# rear_ultrasonic_radar.net
KiCad netlist of a schematic drawn in Altium Designer
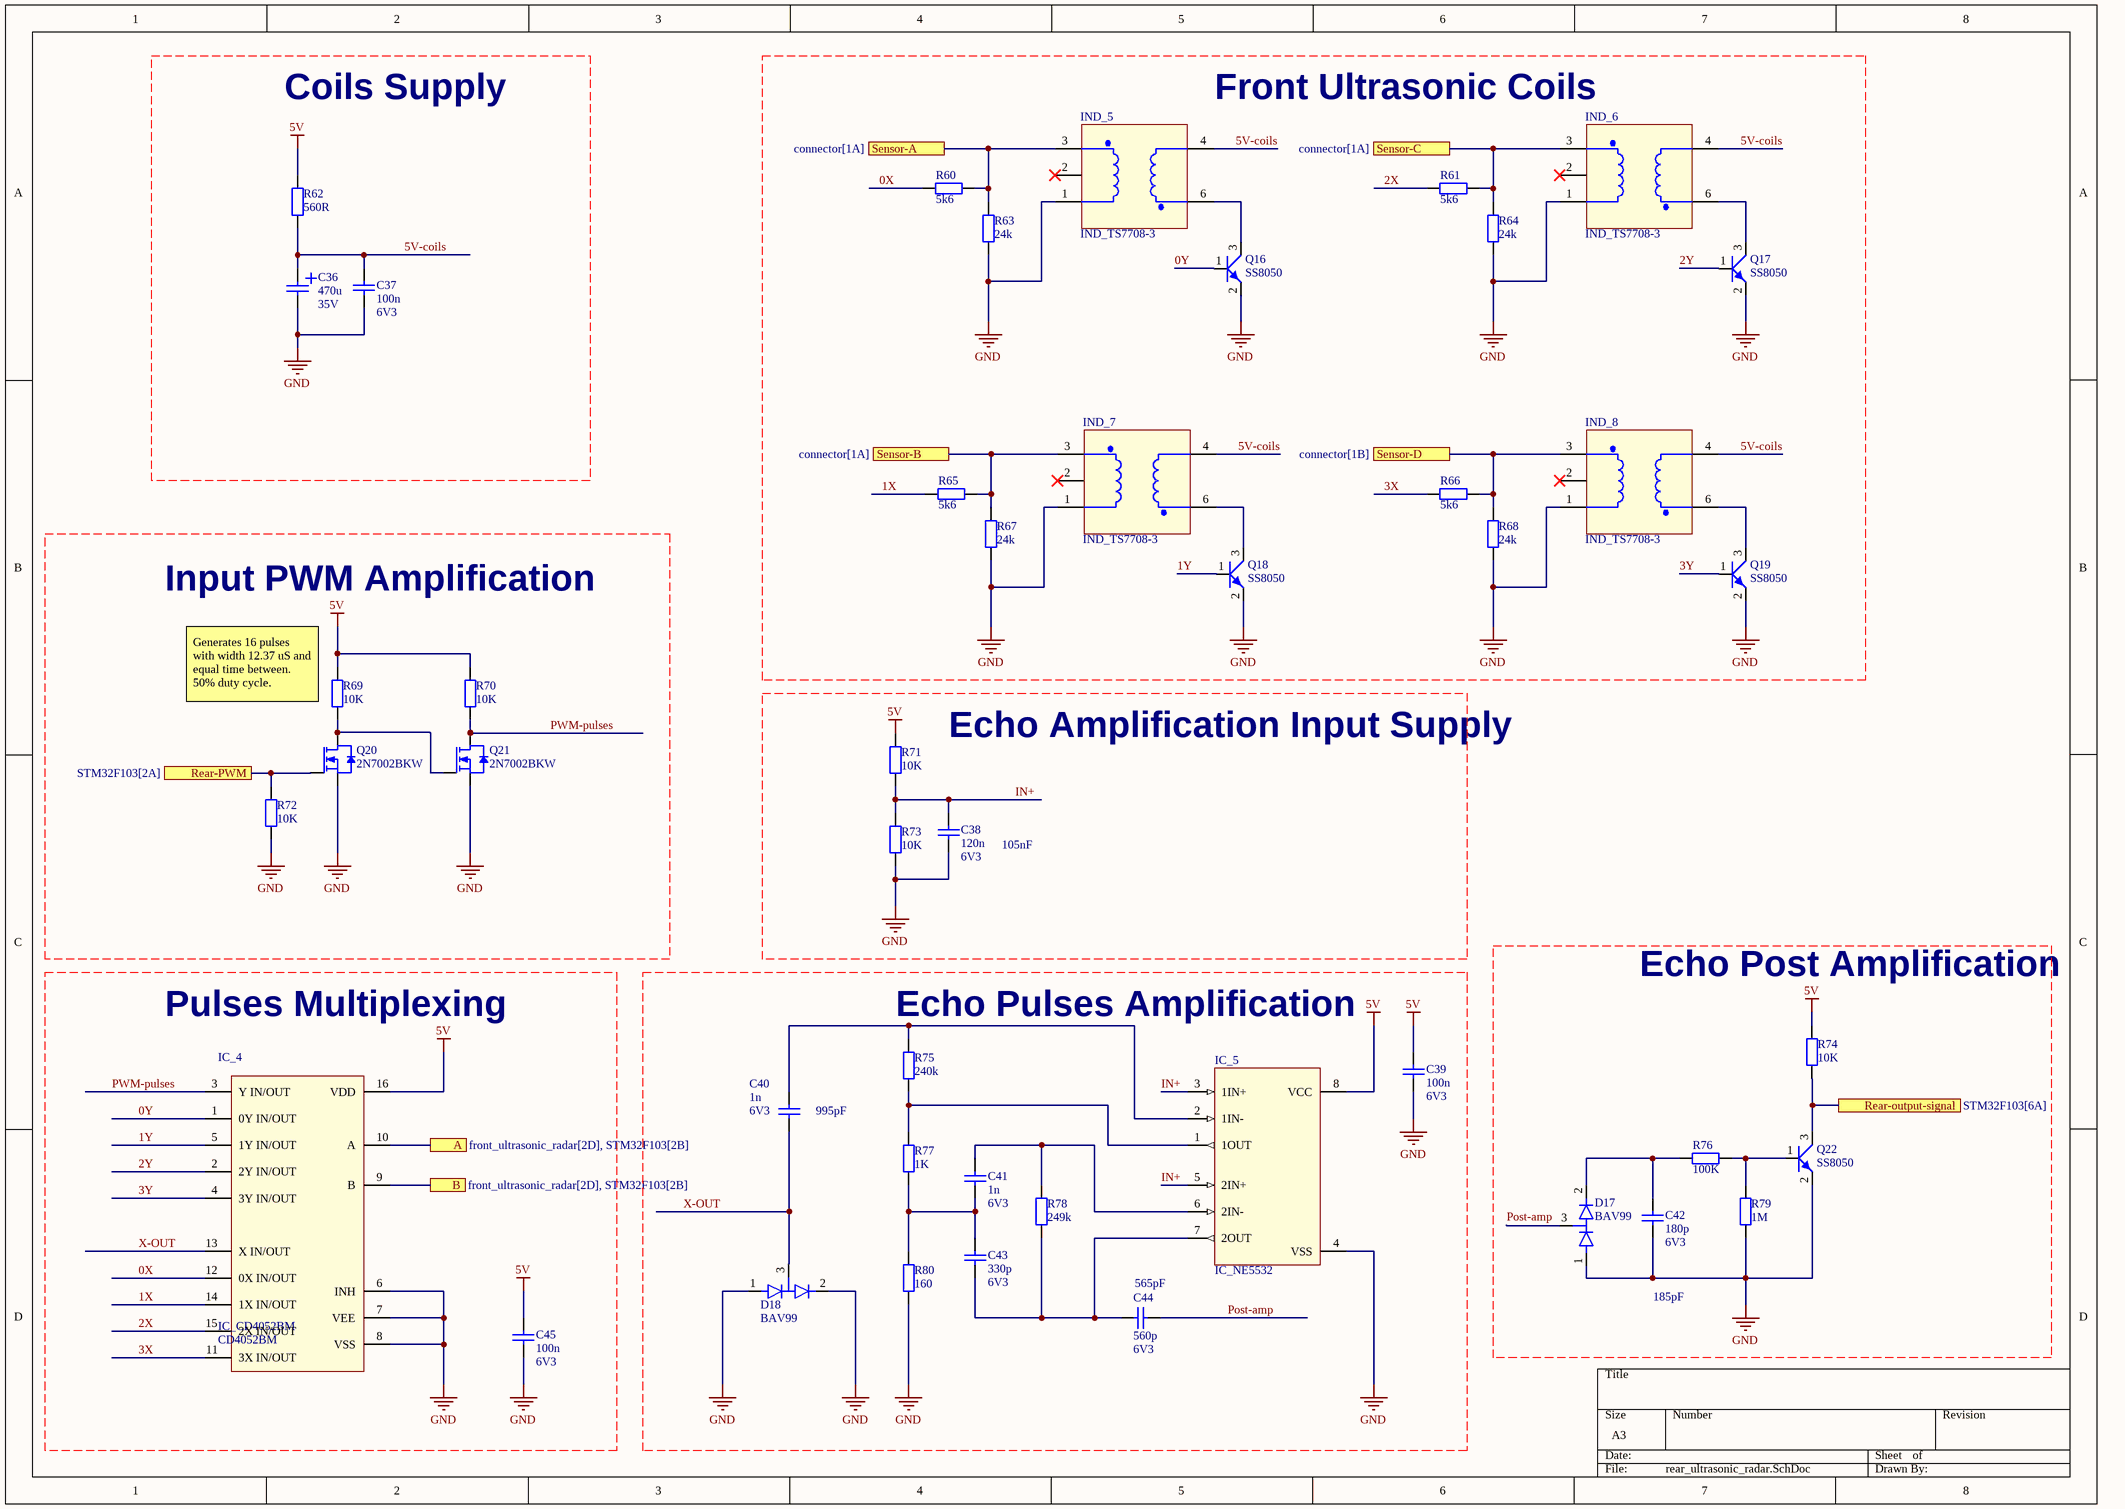
[diagram p0: rear_ultrasonic_radar.SchDoc]

(export (version "E")
  (design (tool "Eeschema 10.0.6"))
  (components
    (comp (ref "C36")
      (value "CAP_POL")
      (footprint "CAP_Panasonic_EEE-FK1V471SP")
      (description "Aluminium Electrolytic Capacitors - SMD 35volts 470uF SMD AEC-Q200 Reflow Only")
      (fields
        (field (name "VALUE1") "470u")
        (field (name "VALUE2") "35V")
        (field (name "MANUFACTURER") "Panasonic")
      )
      (libsource (lib "DSW_Lib") (part "CAP_POL"))
    )
    (comp (ref "C37")
      (value "CAP")
      (footprint "CAPC2012X88N")
      (description "X7R 10% 0805")
      (fields
        (field (name "VALUE1") "100n")
        (field (name "VALUE2") "6V3")
        (field (name "MANUFACTURER") "KEMET")
      )
      (libsource (lib "DSW_Lib") (part "CAP"))
    )
    (comp (ref "C38")
      (value "CAP")
      (footprint "CAPC2012X88N")
      (description "X7R 10% 0805")
      (fields
        (field (name "VALUE1") "120n")
        (field (name "VALUE2") "6V3")
        (field (name "MANUFACTURER") "KEMET")
      )
      (libsource (lib "DSW_Lib") (part "CAP"))
    )
    (comp (ref "C39")
      (value "CAP")
      (footprint "CAPC2012X88N")
      (description "X7R 10% 0805")
      (fields
        (field (name "VALUE1") "100n")
        (field (name "VALUE2") "6V3")
        (field (name "MANUFACTURER") "KEMET")
      )
      (libsource (lib "DSW_Lib") (part "CAP"))
    )
    (comp (ref "C40")
      (value "CAP")
      (footprint "CAPC2012X88N")
      (description "X7R 10% 0805")
      (fields
        (field (name "VALUE1") "1n")
        (field (name "VALUE2") "6V3")
        (field (name "MANUFACTURER") "KEMET")
      )
      (libsource (lib "DSW_Lib") (part "CAP"))
    )
    (comp (ref "C41")
      (value "CAP")
      (footprint "CAPC2012X88N")
      (description "X7R 10% 0805")
      (fields
        (field (name "VALUE1") "1n")
        (field (name "VALUE2") "6V3")
        (field (name "MANUFACTURER") "KEMET")
      )
      (libsource (lib "DSW_Lib") (part "CAP"))
    )
    (comp (ref "C42")
      (value "CAP")
      (footprint "CAPC2012X88N")
      (description "X7R 10% 0805")
      (fields
        (field (name "VALUE1") "180p")
        (field (name "VALUE2") "6V3")
        (field (name "MANUFACTURER") "KEMET")
      )
      (libsource (lib "DSW_Lib") (part "CAP"))
    )
    (comp (ref "C43")
      (value "CAP")
      (footprint "CAPC2012X88N")
      (description "X7R 10% 0805")
      (fields
        (field (name "VALUE1") "330p")
        (field (name "VALUE2") "6V3")
        (field (name "MANUFACTURER") "KEMET")
      )
      (libsource (lib "DSW_Lib") (part "CAP"))
    )
    (comp (ref "C44")
      (value "CAP")
      (footprint "CAPC2012X88N")
      (description "X7R 10% 0805")
      (fields
        (field (name "VALUE1") "560p")
        (field (name "VALUE2") "6V3")
        (field (name "MANUFACTURER") "KEMET")
      )
      (libsource (lib "DSW_Lib") (part "CAP"))
    )
    (comp (ref "C45")
      (value "CAP")
      (footprint "CAPC2012X88N")
      (description "X7R 10% 0805")
      (fields
        (field (name "VALUE1") "100n")
        (field (name "VALUE2") "6V3")
        (field (name "MANUFACTURER") "KEMET")
      )
      (libsource (lib "DSW_Lib") (part "CAP"))
    )
    (comp (ref "D17")
      (value "High-speed double diode")
      (footprint "DIO_BAV99-SOT23")
      (fields (field (name "VALUE1") "BAV99") (field (name "MANUFACTURER") "Philips"))
      (libsource (lib "DSW_Lib") (part "DIO_BAV99"))
    )
    (comp (ref "D18")
      (value "High-speed double diode")
      (footprint "DIO_BAV99-SOT23")
      (fields (field (name "VALUE1") "BAV99") (field (name "MANUFACTURER") "Philips"))
      (libsource (lib "DSW_Lib") (part "DIO_BAV99"))
    )
    (comp (ref "IC_4")
      (value "IC_CD4052BM")
      (footprint "SOP-16")
      (description "Dual 4-Channel Analog Multiplexer/Demultiplexer")
      (fields (field (name "VALUE1") "CD4052BM") (field (name "MANUFACTURER") "Texas Instruments"))
      (libsource (lib "DSW_Lib") (part "IC_CD4052BM"))
    )
    (comp (ref "IC_5")
      (value "IC_NE5532")
      (description "Dual low-noise operational amplifier ")
      (libsource (lib "IC_NE5532") (part "IC_NE5532"))
    )
    (comp (ref "IND_5")
      (value "IND_TS7708-3")
      (description "12times Amplifying Transformer,IFT Inductors for Ultrasonic Sensors")
      (libsource (lib "IND_TS7708-3") (part "IND_TS7708-3"))
    )
    (comp (ref "IND_6")
      (value "IND_TS7708-3")
      (description "12times Amplifying Transformer,IFT Inductors for Ultrasonic Sensors")
      (libsource (lib "IND_TS7708-3") (part "IND_TS7708-3"))
    )
    (comp (ref "IND_7")
      (value "IND_TS7708-3")
      (description "12times Amplifying Transformer,IFT Inductors for Ultrasonic Sensors")
      (libsource (lib "IND_TS7708-3") (part "IND_TS7708-3"))
    )
    (comp (ref "IND_8")
      (value "IND_TS7708-3")
      (description "12times Amplifying Transformer,IFT Inductors for Ultrasonic Sensors")
      (libsource (lib "IND_TS7708-3") (part "IND_TS7708-3"))
    )
    (comp (ref "Q16")
      (value "TRS_NPN_123")
      (footprint "SOT23")
      (description "Bipolar Transistors - BJT NPN TRANSISTOR 1.5A 40V")
      (fields (field (name "VALUE1") "SS8050") (field (name "MANUFACTURER") "KooChin"))
      (libsource (lib "DSW_Lib") (part "TRS_NPN_123"))
    )
    (comp (ref "Q17")
      (value "TRS_NPN_123")
      (footprint "SOT23")
      (description "Bipolar Transistors - BJT NPN TRANSISTOR 1.5A 40V")
      (fields (field (name "VALUE1") "SS8050") (field (name "MANUFACTURER") "KooChin"))
      (libsource (lib "DSW_Lib") (part "TRS_NPN_123"))
    )
    (comp (ref "Q18")
      (value "TRS_NPN_123")
      (footprint "SOT23")
      (description "Bipolar Transistors - BJT NPN TRANSISTOR 1.5A 40V")
      (fields (field (name "VALUE1") "SS8050") (field (name "MANUFACTURER") "KooChin"))
      (libsource (lib "DSW_Lib") (part "TRS_NPN_123"))
    )
    (comp (ref "Q19")
      (value "TRS_NPN_123")
      (footprint "SOT23")
      (description "Bipolar Transistors - BJT NPN TRANSISTOR 1.5A 40V")
      (fields (field (name "VALUE1") "SS8050") (field (name "MANUFACTURER") "KooChin"))
      (libsource (lib "DSW_Lib") (part "TRS_NPN_123"))
    )
    (comp (ref "Q20")
      (value "TRS_FETN_123")
      (footprint "SOT65P210X110-3N")
      (description "NXP - 2N7002BKW - MOSFET, N CH, 60V, 0.31A, SOT323")
      (fields (field (name "VALUE1") "2N7002BKW") (field (name "MANUFACTURER") "NXP"))
      (libsource (lib "DSW_Lib") (part "TRS_FETN_123"))
    )
    (comp (ref "Q21")
      (value "TRS_FETN_123")
      (footprint "SOT65P210X110-3N")
      (description "NXP - 2N7002BKW - MOSFET, N CH, 60V, 0.31A, SOT323")
      (fields (field (name "VALUE1") "2N7002BKW") (field (name "MANUFACTURER") "NXP"))
      (libsource (lib "DSW_Lib") (part "TRS_FETN_123"))
    )
    (comp (ref "Q22")
      (value "TRS_NPN_123")
      (footprint "SOT23")
      (description "Bipolar Transistors - BJT NPN TRANSISTOR 1.5A 40V")
      (fields (field (name "VALUE1") "SS8050") (field (name "MANUFACTURER") "KooChin"))
      (libsource (lib "DSW_Lib") (part "TRS_NPN_123"))
    )
    (comp (ref "R60")
      (value "RES")
      (footprint "RESC2012X60N")
      (description "RESISTOR, 0805, 5k6, 1%, SMD")
      (fields (field (name "VALUE1") "5k6") (field (name "MANUFACTURER") "Yageo"))
      (libsource (lib "") (part "RES_2"))
    )
    (comp (ref "R61")
      (value "RES")
      (footprint "RESC2012X60N")
      (description "RESISTOR, 0805, 5k6, 1%, SMD")
      (fields (field (name "VALUE1") "5k6") (field (name "MANUFACTURER") "Yageo"))
      (libsource (lib "") (part "RES_2"))
    )
    (comp (ref "R62")
      (value "RES")
      (footprint "RESC2012X60N")
      (description "RESISTOR, 0805, 560R, 1%, SMD")
      (fields (field (name "VALUE1") "560R") (field (name "MANUFACTURER") "Yageo"))
      (libsource (lib "DSW_Lib") (part "RES"))
    )
    (comp (ref "R63")
      (value "RES")
      (footprint "RESC2012X60N")
      (description "RESISTOR, 0805, 24k, 1%, SMD")
      (fields (field (name "VALUE1") "24k") (field (name "MANUFACTURER") "Yageo"))
      (libsource (lib "DSW_Lib") (part "RES"))
    )
    (comp (ref "R64")
      (value "RES")
      (footprint "RESC2012X60N")
      (description "RESISTOR, 0805, 24k, 1%, SMD")
      (fields (field (name "VALUE1") "24k") (field (name "MANUFACTURER") "Yageo"))
      (libsource (lib "DSW_Lib") (part "RES"))
    )
    (comp (ref "R65")
      (value "RES")
      (footprint "RESC2012X60N")
      (description "RESISTOR, 0805, 5k6, 1%, SMD")
      (fields (field (name "VALUE1") "5k6") (field (name "MANUFACTURER") "Yageo"))
      (libsource (lib "") (part "RES_2"))
    )
    (comp (ref "R66")
      (value "RES")
      (footprint "RESC2012X60N")
      (description "RESISTOR, 0805, 5k6, 1%, SMD")
      (fields (field (name "VALUE1") "5k6") (field (name "MANUFACTURER") "Yageo"))
      (libsource (lib "") (part "RES_2"))
    )
    (comp (ref "R67")
      (value "RES")
      (footprint "RESC2012X60N")
      (description "RESISTOR, 0805, 24k, 1%, SMD")
      (fields (field (name "VALUE1") "24k") (field (name "MANUFACTURER") "Yageo"))
      (libsource (lib "DSW_Lib") (part "RES"))
    )
    (comp (ref "R68")
      (value "RES")
      (footprint "RESC2012X60N")
      (description "RESISTOR, 0805, 24k, 1%, SMD")
      (fields (field (name "VALUE1") "24k") (field (name "MANUFACTURER") "Yageo"))
      (libsource (lib "DSW_Lib") (part "RES"))
    )
    (comp (ref "R69")
      (value "RES")
      (footprint "RESC2012X60N")
      (description "RESISTOR, 0805, 10K, 1%, SMD")
      (fields (field (name "VALUE1") "10K") (field (name "MANUFACTURER") "Yageo"))
      (libsource (lib "DSW_Lib") (part "RES"))
    )
    (comp (ref "R70")
      (value "RES")
      (footprint "RESC2012X60N")
      (description "RESISTOR, 0805, 10K, 1%, SMD")
      (fields (field (name "VALUE1") "10K") (field (name "MANUFACTURER") "Yageo"))
      (libsource (lib "DSW_Lib") (part "RES"))
    )
    (comp (ref "R71")
      (value "RES")
      (footprint "RESC2012X60N")
      (description "RESISTOR, 0805, 10K, 1%, SMD")
      (fields (field (name "VALUE1") "10K") (field (name "MANUFACTURER") "Yageo"))
      (libsource (lib "") (part "RES_3"))
    )
    (comp (ref "R72")
      (value "RES")
      (footprint "RESC2012X60N")
      (description "RESISTOR, 0805, 10K, 1%, SMD")
      (fields (field (name "VALUE1") "10K") (field (name "MANUFACTURER") "Yageo"))
      (libsource (lib "DSW_Lib") (part "RES"))
    )
    (comp (ref "R73")
      (value "RES")
      (footprint "RESC2012X60N")
      (description "RESISTOR, 0805, 10K, 1%, SMD")
      (fields (field (name "VALUE1") "10K") (field (name "MANUFACTURER") "Yageo"))
      (libsource (lib "DSW_Lib") (part "RES"))
    )
    (comp (ref "R74")
      (value "RES")
      (footprint "RESC2012X60N")
      (description "RESISTOR, 0805, 10K, 1%, SMD")
      (fields (field (name "VALUE1") "10K") (field (name "MANUFACTURER") "Yageo"))
      (libsource (lib "DSW_Lib") (part "RES"))
    )
    (comp (ref "R75")
      (value "RES")
      (footprint "RESC2012X60N")
      (description "RESISTOR, 0805, 240k, 1%, SMD")
      (fields (field (name "VALUE1") "240k") (field (name "MANUFACTURER") "Yageo"))
      (libsource (lib "") (part "RES_3"))
    )
    (comp (ref "R76")
      (value "RES")
      (footprint "RESC2012X60N")
      (description "RESISTOR, 0805, 100K, 1%, SMD")
      (fields (field (name "VALUE1") "100K") (field (name "MANUFACTURER") "Yageo"))
      (libsource (lib "") (part "RES_1"))
    )
    (comp (ref "R77")
      (value "RES")
      (footprint "RESC2012X60N")
      (description "RESISTOR, 0805, 1K, 1%, SMD")
      (fields (field (name "VALUE1") "1K") (field (name "MANUFACTURER") "Yageo"))
      (libsource (lib "DSW_Lib") (part "RES"))
    )
    (comp (ref "R78")
      (value "RES")
      (footprint "RESC2012X60N")
      (description "RESISTOR, 0805, 249k, 1%, SMD")
      (fields (field (name "VALUE1") "249k") (field (name "MANUFACTURER") "Yageo"))
      (libsource (lib "") (part "RES_3"))
    )
    (comp (ref "R79")
      (value "RES")
      (footprint "RESC2012X60N")
      (description "RESISTOR, 0805, 1M, 1%, SMD")
      (fields (field (name "VALUE1") "1M") (field (name "MANUFACTURER") "Yageo"))
      (libsource (lib "DSW_Lib") (part "RES"))
    )
    (comp (ref "R80")
      (value "RES")
      (footprint "RESC2012X60N")
      (description "RESISTOR, 0805, 160, 1%, SMD")
      (fields (field (name "VALUE1") "160") (field (name "MANUFACTURER") "Yageo"))
      (libsource (lib "DSW_Lib") (part "RES"))
    )
  )
  (nets
    (net (code "1") (name "/0X") (class "Default")
      (node (ref "IC_4") (pin "12") (pinfunction "0X_IN/OUT_12") (pintype "passive"))
      (node (ref "R60") (pin "2") (pinfunction "2_2") (pintype "passive"))
    )
    (net (code "2") (name "/0Y") (class "Default")
      (node (ref "IC_4") (pin "1") (pinfunction "0Y_IN/OUT_1") (pintype "passive"))
      (node (ref "Q16") (pin "1") (pinfunction "B_1") (pintype "passive"))
    )
    (net (code "3") (name "/1X") (class "Default")
      (node (ref "IC_4") (pin "14") (pinfunction "1X_IN/OUT_14") (pintype "passive"))
      (node (ref "R65") (pin "2") (pinfunction "2_2") (pintype "passive"))
    )
    (net (code "4") (name "/1Y") (class "Default")
      (node (ref "IC_4") (pin "5") (pinfunction "1Y_IN/OUT_5") (pintype "passive"))
      (node (ref "Q18") (pin "1") (pinfunction "B_1") (pintype "passive"))
    )
    (net (code "5") (name "/2X") (class "Default")
      (node (ref "IC_4") (pin "15") (pinfunction "2X_IN/OUT_15") (pintype "passive"))
      (node (ref "R61") (pin "2") (pinfunction "2_2") (pintype "passive"))
    )
    (net (code "6") (name "/2Y") (class "Default")
      (node (ref "IC_4") (pin "2") (pinfunction "2Y_IN/OUT_2") (pintype "passive"))
      (node (ref "Q17") (pin "1") (pinfunction "B_1") (pintype "passive"))
    )
    (net (code "7") (name "/3X") (class "Default")
      (node (ref "IC_4") (pin "11") (pinfunction "3X_IN/OUT_11") (pintype "passive"))
      (node (ref "R66") (pin "2") (pinfunction "2_2") (pintype "passive"))
    )
    (net (code "8") (name "/3Y") (class "Default")
      (node (ref "IC_4") (pin "4") (pinfunction "3Y_IN/OUT_4") (pintype "passive"))
      (node (ref "Q19") (pin "1") (pinfunction "B_1") (pintype "passive"))
    )
    (net (code "9") (name "/5V-coils") (class "Default")
      (node (ref "C36") (pin "1") (pinfunction "1_1") (pintype "passive"))
      (node (ref "C37") (pin "2") (pinfunction "2_2") (pintype "passive"))
      (node (ref "IND_5") (pin "4") (pinfunction "4_4") (pintype "passive"))
      (node (ref "IND_6") (pin "4") (pinfunction "4_4") (pintype "passive"))
      (node (ref "IND_7") (pin "4") (pinfunction "4_4") (pintype "passive"))
      (node (ref "IND_8") (pin "4") (pinfunction "4_4") (pintype "passive"))
      (node (ref "R62") (pin "1") (pinfunction "1_1") (pintype "passive"))
    )
    (net (code "10") (name "/A") (class "Default")
      (node (ref "IC_4") (pin "10") (pinfunction "A_10") (pintype "passive"))
    )
    (net (code "11") (name "/B") (class "Default")
      (node (ref "IC_4") (pin "9") (pinfunction "B_9") (pintype "passive"))
    )
    (net (code "12") (name "/IN+") (class "Default")
      (node (ref "C38") (pin "2") (pinfunction "2_2") (pintype "passive"))
      (node (ref "IC_5") (pin "3") (pinfunction "1IN+_3") (pintype "input"))
      (node (ref "IC_5") (pin "5") (pinfunction "2IN+_5") (pintype "input"))
      (node (ref "R71") (pin "2") (pinfunction "2_2") (pintype "passive"))
      (node (ref "R73") (pin "2") (pinfunction "2_2") (pintype "passive"))
    )
    (net (code "13") (name "/PWM-pulses") (class "Default")
      (node (ref "IC_4") (pin "3") (pinfunction "Y_IN/OUT_3") (pintype "passive"))
      (node (ref "Q21") (pin "3") (pinfunction "D_3") (pintype "passive"))
      (node (ref "R70") (pin "1") (pinfunction "1_1") (pintype "passive"))
    )
    (net (code "14") (name "/Post-amp") (class "Default")
      (node (ref "C44") (pin "1") (pinfunction "1_1") (pintype "passive"))
      (node (ref "D17") (pin "3") (pinfunction "K_3") (pintype "passive"))
    )
    (net (code "15") (name "/Rear-PWM") (class "Default")
      (node (ref "Q20") (pin "1") (pinfunction "G_1") (pintype "passive"))
      (node (ref "R72") (pin "2") (pinfunction "2_2") (pintype "passive"))
    )
    (net (code "16") (name "/Rear-output-signal") (class "Default")
      (node (ref "Q22") (pin "3") (pinfunction "C_3") (pintype "passive"))
      (node (ref "R74") (pin "1") (pinfunction "1_1") (pintype "passive"))
    )
    (net (code "17") (name "/Sensor-A") (class "Default")
      (node (ref "IND_5") (pin "3") (pinfunction "S2_3") (pintype "passive"))
      (node (ref "R60") (pin "1") (pinfunction "1_1") (pintype "passive"))
      (node (ref "R63") (pin "2") (pinfunction "2_2") (pintype "passive"))
    )
    (net (code "18") (name "/Sensor-B") (class "Default")
      (node (ref "IND_7") (pin "3") (pinfunction "S2_3") (pintype "passive"))
      (node (ref "R65") (pin "1") (pinfunction "1_1") (pintype "passive"))
      (node (ref "R67") (pin "2") (pinfunction "2_2") (pintype "passive"))
    )
    (net (code "19") (name "/Sensor-C") (class "Default")
      (node (ref "IND_6") (pin "3") (pinfunction "S2_3") (pintype "passive"))
      (node (ref "R61") (pin "1") (pinfunction "1_1") (pintype "passive"))
      (node (ref "R64") (pin "2") (pinfunction "2_2") (pintype "passive"))
    )
    (net (code "20") (name "/Sensor-D") (class "Default")
      (node (ref "IND_8") (pin "3") (pinfunction "S2_3") (pintype "passive"))
      (node (ref "R66") (pin "1") (pinfunction "1_1") (pintype "passive"))
      (node (ref "R68") (pin "2") (pinfunction "2_2") (pintype "passive"))
    )
    (net (code "21") (name "/X-OUT") (class "Default")
      (node (ref "C40") (pin "1") (pinfunction "1_1") (pintype "passive"))
      (node (ref "D18") (pin "3") (pinfunction "K_3") (pintype "passive"))
      (node (ref "IC_4") (pin "13") (pinfunction "X_IN/OUT_13") (pintype "passive"))
    )
    (net (code "22") (name "5V") (class "Default")
      (node (ref "C39") (pin "2") (pinfunction "2_2") (pintype "passive"))
      (node (ref "C45") (pin "2") (pinfunction "2_2") (pintype "passive"))
      (node (ref "IC_4") (pin "16") (pinfunction "VDD_16") (pintype "passive"))
      (node (ref "IC_5") (pin "8") (pinfunction "VCC_8") (pintype "power_in"))
      (node (ref "R62") (pin "2") (pinfunction "2_2") (pintype "passive"))
      (node (ref "R69") (pin "2") (pinfunction "2_2") (pintype "passive"))
      (node (ref "R70") (pin "2") (pinfunction "2_2") (pintype "passive"))
      (node (ref "R71") (pin "1") (pinfunction "1_1") (pintype "passive"))
      (node (ref "R74") (pin "2") (pinfunction "2_2") (pintype "passive"))
    )
    (net (code "23") (name "GND") (class "Default")
      (node (ref "C36") (pin "2") (pinfunction "2_2") (pintype "passive"))
      (node (ref "C37") (pin "1") (pinfunction "1_1") (pintype "passive"))
      (node (ref "C38") (pin "1") (pinfunction "1_1") (pintype "passive"))
      (node (ref "C39") (pin "1") (pinfunction "1_1") (pintype "passive"))
      (node (ref "C42") (pin "1") (pinfunction "1_1") (pintype "passive"))
      (node (ref "C45") (pin "1") (pinfunction "1_1") (pintype "passive"))
      (node (ref "D17") (pin "1") (pinfunction "A1_1") (pintype "passive"))
      (node (ref "D18") (pin "1") (pinfunction "A1_1") (pintype "passive"))
      (node (ref "D18") (pin "2") (pinfunction "A2_2") (pintype "passive"))
      (node (ref "IC_4") (pin "6") (pinfunction "INH_6") (pintype "passive"))
      (node (ref "IC_4") (pin "7") (pinfunction "VEE_7") (pintype "passive"))
      (node (ref "IC_4") (pin "8") (pinfunction "VSS_8") (pintype "passive"))
      (node (ref "IC_5") (pin "4") (pinfunction "VSS_4") (pintype "power_in"))
      (node (ref "IND_5") (pin "1") (pinfunction "1_1") (pintype "passive"))
      (node (ref "IND_6") (pin "1") (pinfunction "1_1") (pintype "passive"))
      (node (ref "IND_7") (pin "1") (pinfunction "1_1") (pintype "passive"))
      (node (ref "IND_8") (pin "1") (pinfunction "1_1") (pintype "passive"))
      (node (ref "Q16") (pin "2") (pinfunction "E_2") (pintype "passive"))
      (node (ref "Q17") (pin "2") (pinfunction "E_2") (pintype "passive"))
      (node (ref "Q18") (pin "2") (pinfunction "E_2") (pintype "passive"))
      (node (ref "Q19") (pin "2") (pinfunction "E_2") (pintype "passive"))
      (node (ref "Q20") (pin "2") (pinfunction "S_2") (pintype "passive"))
      (node (ref "Q21") (pin "2") (pinfunction "S_2") (pintype "passive"))
      (node (ref "Q22") (pin "2") (pinfunction "E_2") (pintype "passive"))
      (node (ref "R63") (pin "1") (pinfunction "1_1") (pintype "passive"))
      (node (ref "R64") (pin "1") (pinfunction "1_1") (pintype "passive"))
      (node (ref "R67") (pin "1") (pinfunction "1_1") (pintype "passive"))
      (node (ref "R68") (pin "1") (pinfunction "1_1") (pintype "passive"))
      (node (ref "R72") (pin "1") (pinfunction "1_1") (pintype "passive"))
      (node (ref "R73") (pin "1") (pinfunction "1_1") (pintype "passive"))
      (node (ref "R79") (pin "1") (pinfunction "1_1") (pintype "passive"))
      (node (ref "R80") (pin "1") (pinfunction "1_1") (pintype "passive"))
    )
    (net (code "24") (name "Net-(C41-Pad2)") (class "Default")
      (node (ref "C41") (pin "2") (pinfunction "2_2") (pintype "passive"))
      (node (ref "C43") (pin "2") (pinfunction "2_2") (pintype "passive"))
      (node (ref "R77") (pin "1") (pinfunction "1_1") (pintype "passive"))
      (node (ref "R80") (pin "2") (pinfunction "2_2") (pintype "passive"))
    )
    (net (code "25") (name "Net-(D17-A2)") (class "Default")
      (node (ref "C42") (pin "2") (pinfunction "2_2") (pintype "passive"))
      (node (ref "D17") (pin "2") (pinfunction "A2_2") (pintype "passive"))
      (node (ref "R76") (pin "1") (pinfunction "1_1") (pintype "passive"))
    )
    (net (code "26") (name "Net-(IC_5-1IN-)") (class "Default")
      (node (ref "C40") (pin "2") (pinfunction "2_2") (pintype "passive"))
      (node (ref "IC_5") (pin "2") (pinfunction "1IN-_2") (pintype "input"))
      (node (ref "R75") (pin "1") (pinfunction "1_1") (pintype "passive"))
    )
    (net (code "27") (name "Net-(IC_5-1OUT)") (class "Default")
      (node (ref "IC_5") (pin "1") (pinfunction "1OUT_1") (pintype "output"))
      (node (ref "R75") (pin "2") (pinfunction "2_2") (pintype "passive"))
      (node (ref "R77") (pin "2") (pinfunction "2_2") (pintype "passive"))
    )
    (net (code "28") (name "Net-(IC_5-2IN-)") (class "Default")
      (node (ref "C41") (pin "1") (pinfunction "1_1") (pintype "passive"))
      (node (ref "IC_5") (pin "6") (pinfunction "2IN-_6") (pintype "input"))
      (node (ref "R78") (pin "1") (pinfunction "1_1") (pintype "passive"))
    )
    (net (code "29") (name "Net-(IC_5-2OUT)") (class "Default")
      (node (ref "C43") (pin "1") (pinfunction "1_1") (pintype "passive"))
      (node (ref "C44") (pin "2") (pinfunction "2_2") (pintype "passive"))
      (node (ref "IC_5") (pin "7") (pinfunction "2OUT_7") (pintype "output"))
      (node (ref "R78") (pin "2") (pinfunction "2_2") (pintype "passive"))
    )
    (net (code "30") (name "Net-(IND_5-S1)") (class "Default")
      (node (ref "IND_5") (pin "6") (pinfunction "S1_6") (pintype "passive"))
      (node (ref "Q16") (pin "3") (pinfunction "C_3") (pintype "passive"))
    )
    (net (code "31") (name "Net-(IND_6-S1)") (class "Default")
      (node (ref "IND_6") (pin "6") (pinfunction "S1_6") (pintype "passive"))
      (node (ref "Q17") (pin "3") (pinfunction "C_3") (pintype "passive"))
    )
    (net (code "32") (name "Net-(IND_7-S1)") (class "Default")
      (node (ref "IND_7") (pin "6") (pinfunction "S1_6") (pintype "passive"))
      (node (ref "Q18") (pin "3") (pinfunction "C_3") (pintype "passive"))
    )
    (net (code "33") (name "Net-(IND_8-S1)") (class "Default")
      (node (ref "IND_8") (pin "6") (pinfunction "S1_6") (pintype "passive"))
      (node (ref "Q19") (pin "3") (pinfunction "C_3") (pintype "passive"))
    )
    (net (code "34") (name "Net-(Q20-D)") (class "Default")
      (node (ref "Q20") (pin "3") (pinfunction "D_3") (pintype "passive"))
      (node (ref "Q21") (pin "1") (pinfunction "G_1") (pintype "passive"))
      (node (ref "R69") (pin "1") (pinfunction "1_1") (pintype "passive"))
    )
    (net (code "35") (name "Net-(Q22-B)") (class "Default")
      (node (ref "Q22") (pin "1") (pinfunction "B_1") (pintype "passive"))
      (node (ref "R76") (pin "2") (pinfunction "2_2") (pintype "passive"))
      (node (ref "R79") (pin "2") (pinfunction "2_2") (pintype "passive"))
    )
    (net (code "36") (name "unconnected-(IND_5-Pad2)") (class "Default")
      (node (ref "IND_5") (pin "2") (pinfunction "2_2") (pintype "passive+no_connect"))
    )
    (net (code "37") (name "unconnected-(IND_6-Pad2)") (class "Default")
      (node (ref "IND_6") (pin "2") (pinfunction "2_2") (pintype "passive+no_connect"))
    )
    (net (code "38") (name "unconnected-(IND_7-Pad2)") (class "Default")
      (node (ref "IND_7") (pin "2") (pinfunction "2_2") (pintype "passive+no_connect"))
    )
    (net (code "39") (name "unconnected-(IND_8-Pad2)") (class "Default")
      (node (ref "IND_8") (pin "2") (pinfunction "2_2") (pintype "passive+no_connect"))
    )
  )
)
